# i2cstump.net
KiCad netlist of a schematic drawn in EAGLE
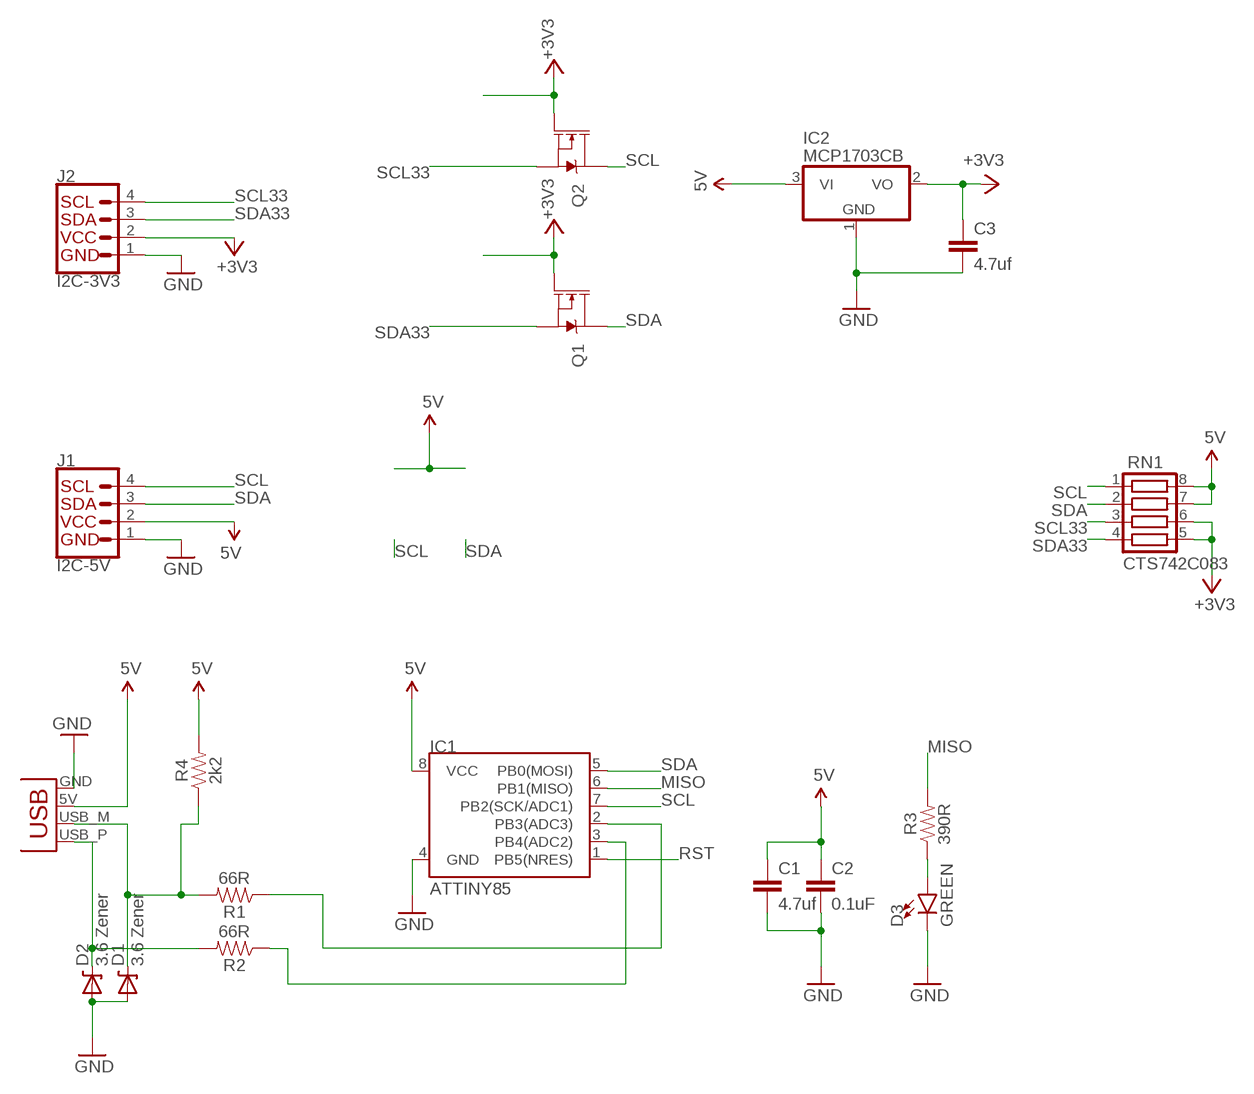
[diagram p0: schematic, sheet 1]

(export (version "E")
  (design (tool "Eeschema 10.0.6"))
  (components
    (comp (ref "C1")
      (value "4.7uf")
      (footprint "eagle-import:0805")
      (libsource (lib "eagle-import") (part "CAP0805"))
    )
    (comp (ref "C2")
      (value "0.1uF")
      (footprint "eagle-import:0603")
      (libsource (lib "eagle-import") (part "0.1UF-0603-25V-(+80/-20%)"))
    )
    (comp (ref "C3")
      (value "4.7uf")
      (footprint "eagle-import:0805")
      (libsource (lib "eagle-import") (part "CAP0805"))
    )
    (comp (ref "D1")
      (value "3.6 Zener")
      (footprint "eagle-import:SOD-323")
      (libsource (lib "eagle-import") (part "DIODE-ZENER-BZT52"))
    )
    (comp (ref "D2")
      (value "3.6 Zener")
      (footprint "eagle-import:SOD-323")
      (libsource (lib "eagle-import") (part "DIODE-ZENER-BZT52"))
    )
    (comp (ref "D3")
      (value "GREEN")
      (footprint "eagle-import:LED-0603")
      (libsource (lib "eagle-import") (part "LED-GREEN0603"))
    )
    (comp (ref "IC1")
      (value "ATTINY85")
      (footprint "eagle-import:SO08-EIAJ")
      (libsource (lib "eagle-import") (part "ATTINY45"))
    )
    (comp (ref "IC2")
      (value "MCP1703CB")
      (footprint "eagle-import:SOT23")
      (libsource (lib "eagle-import") (part "MCP1703CB"))
    )
    (comp (ref "J1")
      (value "I2C-5V")
      (footprint "eagle-import:1X04_1MM_RA")
      (libsource (lib "eagle-import") (part "QWIIC_CONNECTORJS-1MM"))
    )
    (comp (ref "J2")
      (value "I2C-3V3")
      (footprint "eagle-import:1X04_1MM_RA")
      (libsource (lib "eagle-import") (part "QWIIC_CONNECTORJS-1MM"))
    )
    (comp (ref "Q1")
      (value "220mA/50V/3.5Ω")
      (footprint "eagle-import:SOT23-3")
      (libsource (lib "eagle-import") (part "MOSFET-NCH-BSS138"))
    )
    (comp (ref "Q2")
      (value "220mA/50V/3.5Ω")
      (footprint "eagle-import:SOT23-3")
      (libsource (lib "eagle-import") (part "MOSFET-NCH-BSS138"))
    )
    (comp (ref "R1")
      (value "66R")
      (footprint "eagle-import:0603")
      (libsource (lib "eagle-import") (part "RESISTOR0603"))
    )
    (comp (ref "R2")
      (value "66R")
      (footprint "eagle-import:0603")
      (libsource (lib "eagle-import") (part "RESISTOR0603"))
    )
    (comp (ref "R3")
      (value "390R")
      (footprint "eagle-import:0603")
      (libsource (lib "eagle-import") (part "RESISTOR0603"))
    )
    (comp (ref "R4")
      (value "2k2")
      (footprint "eagle-import:0603")
      (libsource (lib "eagle-import") (part "RESISTOR0603"))
    )
    (comp (ref "RN1")
      (value "CTS742C083")
      (footprint "eagle-import:CTS742C083")
      (libsource (lib "eagle-import") (part "CTS742C083"))
    )
    (comp (ref "X1")
      (value "USBPCB")
      (footprint "eagle-import:USB-A-PCB")
      (libsource (lib "eagle-import") (part "USBPCB"))
    )
  )
  (nets
    (net (code "1") (name "+3V3") (class "Default")
      (node (ref "C3") (pin "1") (pinfunction "1_1") (pintype "passive"))
      (node (ref "IC2") (pin "2") (pinfunction "VO_2") (pintype "passive"))
      (node (ref "J2") (pin "2") (pinfunction "VCC_2") (pintype "power_in"))
      (node (ref "Q1") (pin "1") (pinfunction "G_1") (pintype "bidirectional"))
      (node (ref "Q2") (pin "1") (pinfunction "G_1") (pintype "bidirectional"))
      (node (ref "RN1") (pin "5") (pinfunction "5_5") (pintype "passive"))
      (node (ref "RN1") (pin "6") (pinfunction "6_6") (pintype "passive"))
    )
    (net (code "2") (name "/MISO") (class "Default")
      (node (ref "IC1") (pin "6") (pinfunction "PB1(MISO)_6") (pintype "bidirectional"))
      (node (ref "R3") (pin "2") (pinfunction "2_2") (pintype "passive"))
    )
    (net (code "3") (name "/RST") (class "Default")
      (node (ref "IC1") (pin "1") (pinfunction "PB5(NRES)_1") (pintype "bidirectional"))
    )
    (net (code "4") (name "/SCL") (class "Default")
      (node (ref "IC1") (pin "7") (pinfunction "PB2(SCK/ADC1)_7") (pintype "bidirectional"))
      (node (ref "J1") (pin "4") (pinfunction "SCL_4") (pintype "passive"))
      (node (ref "Q2") (pin "3") (pinfunction "D_3") (pintype "bidirectional"))
      (node (ref "RN1") (pin "1") (pinfunction "1_1") (pintype "passive"))
    )
    (net (code "5") (name "/SCL33") (class "Default")
      (node (ref "J2") (pin "4") (pinfunction "SCL_4") (pintype "passive"))
      (node (ref "Q2") (pin "2") (pinfunction "S_2") (pintype "bidirectional"))
      (node (ref "RN1") (pin "3") (pinfunction "3_3") (pintype "passive"))
    )
    (net (code "6") (name "/SDA") (class "Default")
      (node (ref "IC1") (pin "5") (pinfunction "PB0(MOSI)_5") (pintype "bidirectional"))
      (node (ref "J1") (pin "3") (pinfunction "SDA_3") (pintype "passive"))
      (node (ref "Q1") (pin "3") (pinfunction "D_3") (pintype "bidirectional"))
      (node (ref "RN1") (pin "2") (pinfunction "2_2") (pintype "passive"))
    )
    (net (code "7") (name "/SDA33") (class "Default")
      (node (ref "J2") (pin "3") (pinfunction "SDA_3") (pintype "passive"))
      (node (ref "Q1") (pin "2") (pinfunction "S_2") (pintype "bidirectional"))
      (node (ref "RN1") (pin "4") (pinfunction "4_4") (pintype "passive"))
    )
    (net (code "8") (name "5V") (class "Default")
      (node (ref "C1") (pin "1") (pinfunction "1_1") (pintype "passive"))
      (node (ref "C2") (pin "1") (pinfunction "1_1") (pintype "passive"))
      (node (ref "IC1") (pin "8") (pinfunction "VCC_8") (pintype "bidirectional"))
      (node (ref "IC2") (pin "3") (pinfunction "VI_3") (pintype "input"))
      (node (ref "J1") (pin "2") (pinfunction "VCC_2") (pintype "power_in"))
      (node (ref "R4") (pin "2") (pinfunction "2_2") (pintype "passive"))
      (node (ref "RN1") (pin "7") (pinfunction "7_7") (pintype "passive"))
      (node (ref "RN1") (pin "8") (pinfunction "8_8") (pintype "passive"))
      (node (ref "X1") (pin "5V") (pinfunction "VBUS_5V") (pintype "bidirectional"))
    )
    (net (code "9") (name "GND") (class "Default")
      (node (ref "C1") (pin "2") (pinfunction "2_2") (pintype "passive"))
      (node (ref "C2") (pin "2") (pinfunction "2_2") (pintype "passive"))
      (node (ref "C3") (pin "2") (pinfunction "2_2") (pintype "passive"))
      (node (ref "D1") (pin "2") (pinfunction "A_2") (pintype "passive"))
      (node (ref "D2") (pin "2") (pinfunction "A_2") (pintype "passive"))
      (node (ref "D3") (pin "C") (pinfunction "C_C") (pintype "passive"))
      (node (ref "IC1") (pin "4") (pinfunction "GND_4") (pintype "bidirectional"))
      (node (ref "IC2") (pin "1") (pinfunction "GND_1") (pintype "passive"))
      (node (ref "J1") (pin "1") (pinfunction "GND_1") (pintype "power_in"))
      (node (ref "J2") (pin "1") (pinfunction "GND_1") (pintype "power_in"))
      (node (ref "X1") (pin "GND") (pinfunction "GND_GND") (pintype "bidirectional"))
    )
    (net (code "10") (name "Net-(D1-C)") (class "Default")
      (node (ref "D1") (pin "1") (pinfunction "C_1") (pintype "passive"))
      (node (ref "R1") (pin "2") (pinfunction "2_2") (pintype "passive"))
      (node (ref "R4") (pin "1") (pinfunction "1_1") (pintype "passive"))
      (node (ref "X1") (pin "USB_M") (pinfunction "D-_USB_M") (pintype "bidirectional"))
    )
    (net (code "11") (name "Net-(D2-C)") (class "Default")
      (node (ref "D2") (pin "1") (pinfunction "C_1") (pintype "passive"))
      (node (ref "R2") (pin "2") (pinfunction "2_2") (pintype "passive"))
      (node (ref "X1") (pin "USB_P") (pinfunction "D+_USB_P") (pintype "bidirectional"))
    )
    (net (code "12") (name "Net-(D3-PadA)") (class "Default")
      (node (ref "D3") (pin "A") (pinfunction "A_A") (pintype "passive"))
      (node (ref "R3") (pin "1") (pinfunction "1_1") (pintype "passive"))
    )
    (net (code "13") (name "Net-(IC1-PB3(ADC3))") (class "Default")
      (node (ref "IC1") (pin "2") (pinfunction "PB3(ADC3)_2") (pintype "bidirectional"))
      (node (ref "R1") (pin "1") (pinfunction "1_1") (pintype "passive"))
    )
    (net (code "14") (name "Net-(IC1-PB4(ADC2))") (class "Default")
      (node (ref "IC1") (pin "3") (pinfunction "PB4(ADC2)_3") (pintype "bidirectional"))
      (node (ref "R2") (pin "1") (pinfunction "1_1") (pintype "passive"))
    )
  )
)
